# Final_5_1.net
KiCad netlist of a schematic drawn in EAGLE
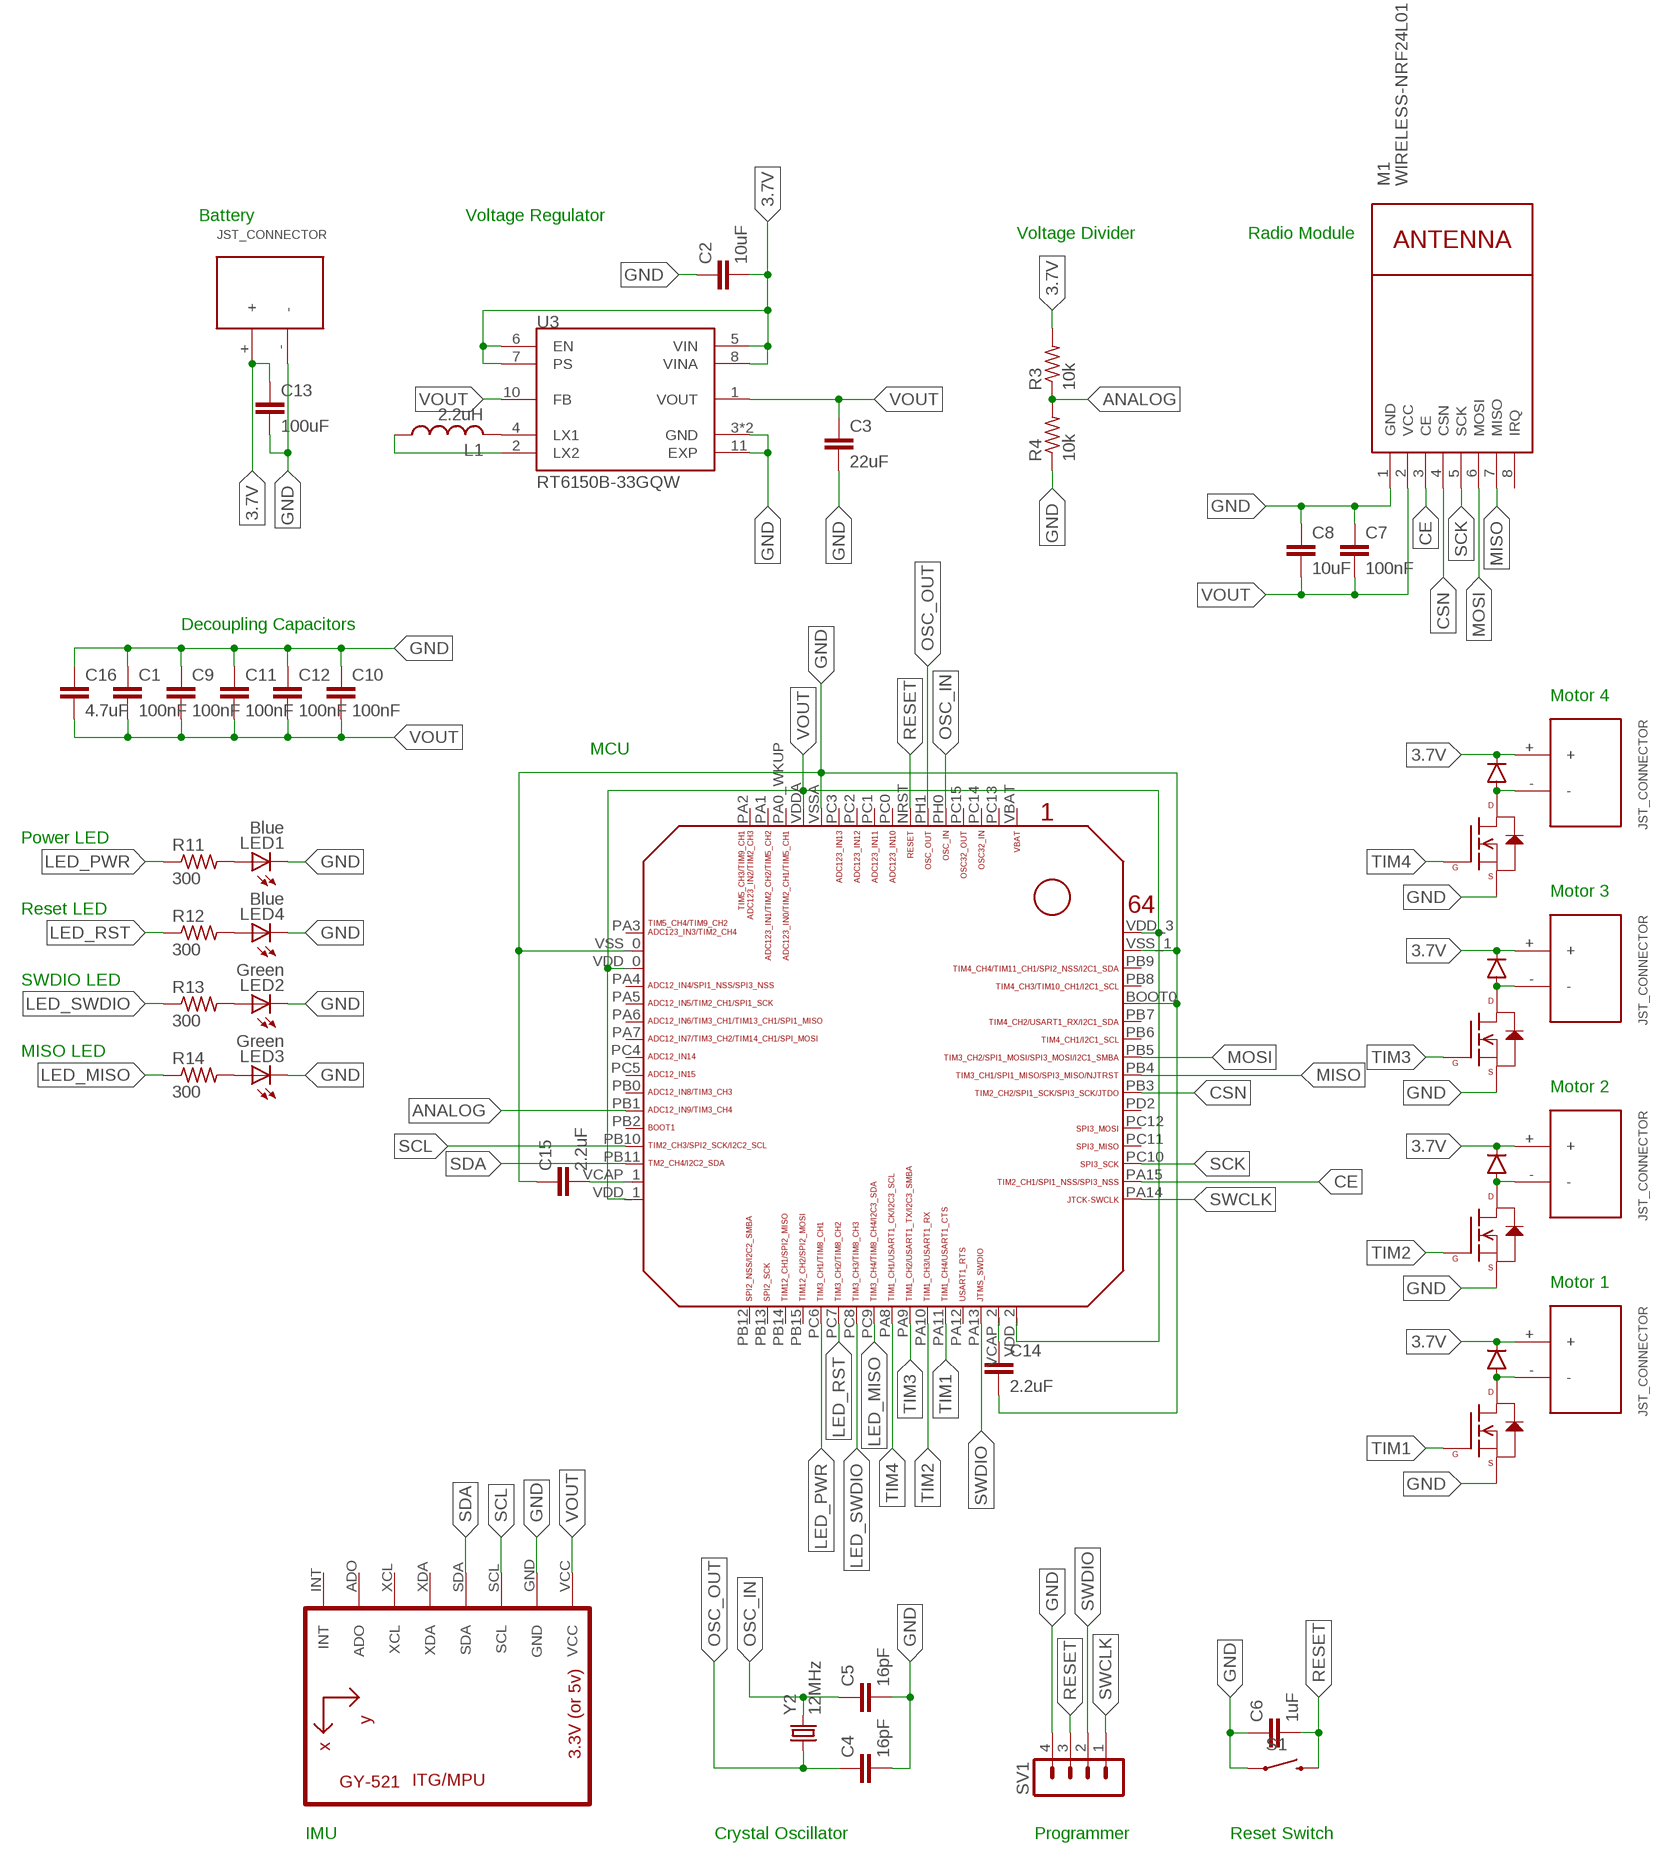
[diagram p0: schematic, sheet 1]

(export (version "E")
  (design (tool "Eeschema 10.0.6"))
  (components
    (comp (ref "C1")
      (value "100nF")
      (footprint "eagle-import:C0603")
      (libsource (lib "eagle-import") (part "rcl_334_C-EUC0603"))
    )
    (comp (ref "C2")
      (value "10uF")
      (footprint "eagle-import:C0603")
      (libsource (lib "eagle-import") (part "rcl_334_C-EUC0603"))
    )
    (comp (ref "C3")
      (value "22uF")
      (footprint "eagle-import:C0603")
      (libsource (lib "eagle-import") (part "rcl_334_C-EUC0603"))
    )
    (comp (ref "C4")
      (value "16pF")
      (footprint "eagle-import:C0603")
      (libsource (lib "eagle-import") (part "rcl_334_C-EUC0603"))
    )
    (comp (ref "C5")
      (value "16pF")
      (footprint "eagle-import:C0603")
      (libsource (lib "eagle-import") (part "rcl_334_C-EUC0603"))
    )
    (comp (ref "C6")
      (value "1uF")
      (footprint "eagle-import:C0603")
      (libsource (lib "eagle-import") (part "rcl_334_C-EUC0603"))
    )
    (comp (ref "C7")
      (value "100nF")
      (footprint "eagle-import:C0603")
      (libsource (lib "eagle-import") (part "rcl_334_C-EUC0603"))
    )
    (comp (ref "C8")
      (value "10uF")
      (footprint "eagle-import:C0603")
      (libsource (lib "eagle-import") (part "rcl_334_C-EUC0603"))
    )
    (comp (ref "C9")
      (value "100nF")
      (footprint "eagle-import:C0603")
      (libsource (lib "eagle-import") (part "rcl_334_C-EUC0603"))
    )
    (comp (ref "C10")
      (value "100nF")
      (footprint "eagle-import:C0603")
      (libsource (lib "eagle-import") (part "rcl_334_C-EUC0603"))
    )
    (comp (ref "C11")
      (value "100nF")
      (footprint "eagle-import:C0603")
      (libsource (lib "eagle-import") (part "rcl_334_C-EUC0603"))
    )
    (comp (ref "C12")
      (value "100nF")
      (footprint "eagle-import:C0603")
      (libsource (lib "eagle-import") (part "rcl_334_C-EUC0603"))
    )
    (comp (ref "C13")
      (value "100uF")
      (footprint "eagle-import:C1206")
      (libsource (lib "eagle-import") (part "rcl_334_C-EUC1206"))
    )
    (comp (ref "C14")
      (value "2.2uF")
      (footprint "eagle-import:C0603")
      (libsource (lib "eagle-import") (part "C-EUC0603"))
    )
    (comp (ref "C15")
      (value "2.2uF")
      (footprint "eagle-import:C0603")
      (libsource (lib "eagle-import") (part "C-EUC0603"))
    )
    (comp (ref "C16")
      (value "4.7uF")
      (footprint "eagle-import:C0603")
      (libsource (lib "eagle-import") (part "rcl_334_C-EUC0603"))
    )
    (comp (ref "L1")
      (value "2.2uH")
      (footprint "eagle-import:L0603")
      (libsource (lib "eagle-import") (part "L-USL0603"))
    )
    (comp (ref "LED1")
      (value "Blue")
      (footprint "eagle-import:CHIP-LED0603")
      (libsource (lib "eagle-import") (part "LEDCHIP-LED0603"))
    )
    (comp (ref "LED2")
      (value "Green")
      (footprint "eagle-import:CHIP-LED0603")
      (libsource (lib "eagle-import") (part "LEDCHIP-LED0603"))
    )
    (comp (ref "LED3")
      (value "Green")
      (footprint "eagle-import:CHIP-LED0603")
      (libsource (lib "eagle-import") (part "LEDCHIP-LED0603"))
    )
    (comp (ref "LED4")
      (value "Blue")
      (footprint "eagle-import:CHIP-LED0603")
      (libsource (lib "eagle-import") (part "LEDCHIP-LED0603"))
    )
    (comp (ref "M1")
      (value "WIRELESS-NRF24L01")
      (footprint "eagle-import:WIRELESS-NRF24L01")
      (libsource (lib "eagle-import") (part "WIRELESS-NRF24L01"))
    )
    (comp (ref "R3")
      (value "10k")
      (footprint "eagle-import:R0603")
      (libsource (lib "eagle-import") (part "R-US_R0603"))
    )
    (comp (ref "R4")
      (value "10k")
      (footprint "eagle-import:R0603")
      (libsource (lib "eagle-import") (part "R-US_R0603"))
    )
    (comp (ref "R11")
      (value "300")
      (footprint "eagle-import:R0603")
      (libsource (lib "eagle-import") (part "R-US_R0603"))
    )
    (comp (ref "R12")
      (value "300")
      (footprint "eagle-import:R0603")
      (libsource (lib "eagle-import") (part "R-US_R0603"))
    )
    (comp (ref "R13")
      (value "300")
      (footprint "eagle-import:R0603")
      (libsource (lib "eagle-import") (part "R-US_R0603"))
    )
    (comp (ref "R14")
      (value "300")
      (footprint "eagle-import:R0603")
      (libsource (lib "eagle-import") (part "R-US_R0603"))
    )
    (comp (ref "S1")
      (value "SWITCH-MOMENTARY-2SMD")
      (footprint "eagle-import:TACTILE-SWITCH-SMD")
      (libsource (lib "eagle-import") (part "SWITCH-MOMENTARY-2SMD"))
    )
    (comp (ref "SV1")
      (value "MA04-1")
      (footprint "eagle-import:MA04-1")
      (libsource (lib "eagle-import") (part "MA04-1"))
    )
    (comp (ref "U$1")
      (value "STM32F405/415_LQFP64")
      (footprint "eagle-import:STM32F405_415_LQFP64")
      (libsource (lib "eagle-import") (part "STM32F405/415_LQFP64"))
    )
    (comp (ref "U$2")
      (value "JST_CONNECTOR_FEMALE")
      (footprint "eagle-import:JST_CONNECTOR_FEMALE")
      (libsource (lib "eagle-import") (part "JST_CONNECTOR_FEMALE"))
    )
    (comp (ref "U$3")
      (value "JST_CONNECTOR_FEMALE")
      (footprint "eagle-import:JST_CONNECTOR_FEMALE")
      (libsource (lib "eagle-import") (part "JST_CONNECTOR_FEMALE"))
    )
    (comp (ref "U$4")
      (value "JST_CONNECTOR_FEMALE")
      (footprint "eagle-import:JST_CONNECTOR_FEMALE")
      (libsource (lib "eagle-import") (part "JST_CONNECTOR_FEMALE"))
    )
    (comp (ref "U$5")
      (value "JST_CONNECTOR_FEMALE")
      (footprint "eagle-import:JST_CONNECTOR_FEMALE")
      (libsource (lib "eagle-import") (part "JST_CONNECTOR_FEMALE"))
    )
    (comp (ref "U$6")
      (value "JST_CONNECTOR_FEMALE")
      (footprint "eagle-import:JST_CONNECTOR_FEMALE")
      (libsource (lib "eagle-import") (part "JST_CONNECTOR_FEMALE"))
    )
    (comp (ref "U$7")
      (value "N-CHANNEL-MOSFET-IRLML6244TRPBF")
      (footprint "eagle-import:SOT23-3")
      (libsource (lib "eagle-import") (part "N-CHANNEL-MOSFET-IRLML6244TRPBF"))
    )
    (comp (ref "U$8")
      (value "N-CHANNEL-MOSFET-IRLML6244TRPBF")
      (footprint "eagle-import:SOT23-3")
      (libsource (lib "eagle-import") (part "N-CHANNEL-MOSFET-IRLML6244TRPBF"))
    )
    (comp (ref "U$9")
      (value "N-CHANNEL-MOSFET-IRLML6244TRPBF")
      (footprint "eagle-import:SOT23-3")
      (libsource (lib "eagle-import") (part "N-CHANNEL-MOSFET-IRLML6244TRPBF"))
    )
    (comp (ref "U$10")
      (value "N-CHANNEL-MOSFET-IRLML6244TRPBF")
      (footprint "eagle-import:SOT23-3")
      (libsource (lib "eagle-import") (part "N-CHANNEL-MOSFET-IRLML6244TRPBF"))
    )
    (comp (ref "U$11")
      (value "DB2W40300L")
      (footprint "eagle-import:MINI2-F3-B")
      (libsource (lib "eagle-import") (part "DB2W40300L"))
    )
    (comp (ref "U$12")
      (value "DB2W40300L")
      (footprint "eagle-import:MINI2-F3-B")
      (libsource (lib "eagle-import") (part "DB2W40300L"))
    )
    (comp (ref "U$13")
      (value "DB2W40300L")
      (footprint "eagle-import:MINI2-F3-B")
      (libsource (lib "eagle-import") (part "DB2W40300L"))
    )
    (comp (ref "U$14")
      (value "DB2W40300L")
      (footprint "eagle-import:MINI2-F3-B")
      (libsource (lib "eagle-import") (part "DB2W40300L"))
    )
    (comp (ref "U2")
      (value "GY-521MPU6050")
      (footprint "eagle-import:GY-521")
      (libsource (lib "eagle-import") (part "GY-521MPU6050"))
    )
    (comp (ref "U3")
      (value "RT6150B-33GQW")
      (footprint "eagle-import:SON50P250X250X80-11N")
      (fields (field (name "DIGI-KEY_PART_NUMBER") "RT6150B-33GQWCT-ND") (field (name "MF") "Richtek USA"))
      (libsource (lib "eagle-import") (part "RT6150B-33GQW"))
    )
    (comp (ref "Y2")
      (value "12MHz")
      (footprint "eagle-import:HC49UP")
      (libsource (lib "eagle-import") (part "CRYSTALSMD"))
    )
  )
  (nets
    (net (code "1") (name "3.7V") (class "Default")
      (node (ref "C13") (pin "1") (pinfunction "1_1") (pintype "passive"))
      (node (ref "C2") (pin "2") (pinfunction "2_2") (pintype "passive"))
      (node (ref "R3") (pin "2") (pinfunction "2_2") (pintype "passive"))
      (node (ref "U$11") (pin "NEG") (pinfunction "GPIN_NEG") (pintype "passive"))
      (node (ref "U$12") (pin "NEG") (pinfunction "GPIN_NEG") (pintype "passive"))
      (node (ref "U$13") (pin "NEG") (pinfunction "GPIN_NEG") (pintype "passive"))
      (node (ref "U$14") (pin "NEG") (pinfunction "GPIN_NEG") (pintype "passive"))
      (node (ref "U$2") (pin "+") (pinfunction "+_+") (pintype "bidirectional"))
      (node (ref "U$3") (pin "+") (pinfunction "+_+") (pintype "bidirectional"))
      (node (ref "U$4") (pin "+") (pinfunction "+_+") (pintype "bidirectional"))
      (node (ref "U$5") (pin "+") (pinfunction "+_+") (pintype "bidirectional"))
      (node (ref "U$6") (pin "+") (pinfunction "+_+") (pintype "bidirectional"))
      (node (ref "U3") (pin "5") (pinfunction "VIN_5") (pintype "power_in"))
      (node (ref "U3") (pin "6") (pinfunction "EN_6") (pintype "input"))
      (node (ref "U3") (pin "7") (pinfunction "PS_7") (pintype "input"))
      (node (ref "U3") (pin "8") (pinfunction "VINA_8") (pintype "power_in"))
    )
    (net (code "2") (name "ANALOG") (class "Default")
      (node (ref "R3") (pin "1") (pinfunction "1_1") (pintype "passive"))
      (node (ref "R4") (pin "2") (pinfunction "2_2") (pintype "passive"))
      (node (ref "U$1") (pin "PB1") (pinfunction "PB1_PB1") (pintype "bidirectional"))
    )
    (net (code "3") (name "CE") (class "Default")
      (node (ref "M1") (pin "3") (pinfunction "CE_3") (pintype "bidirectional"))
      (node (ref "U$1") (pin "PA15") (pinfunction "PA15_PA15") (pintype "bidirectional"))
    )
    (net (code "4") (name "CSN") (class "Default")
      (node (ref "M1") (pin "4") (pinfunction "CSN_4") (pintype "bidirectional"))
      (node (ref "U$1") (pin "PB3") (pinfunction "PB3_PB3") (pintype "bidirectional"))
    )
    (net (code "5") (name "GND") (class "Default")
      (node (ref "C1") (pin "1") (pinfunction "1_1") (pintype "passive"))
      (node (ref "C10") (pin "1") (pinfunction "1_1") (pintype "passive"))
      (node (ref "C11") (pin "1") (pinfunction "1_1") (pintype "passive"))
      (node (ref "C12") (pin "1") (pinfunction "1_1") (pintype "passive"))
      (node (ref "C13") (pin "2") (pinfunction "2_2") (pintype "passive"))
      (node (ref "C14") (pin "2") (pinfunction "2_2") (pintype "passive"))
      (node (ref "C15") (pin "1") (pinfunction "1_1") (pintype "passive"))
      (node (ref "C16") (pin "1") (pinfunction "1_1") (pintype "passive"))
      (node (ref "C2") (pin "1") (pinfunction "1_1") (pintype "passive"))
      (node (ref "C3") (pin "2") (pinfunction "2_2") (pintype "passive"))
      (node (ref "C4") (pin "2") (pinfunction "2_2") (pintype "passive"))
      (node (ref "C5") (pin "2") (pinfunction "2_2") (pintype "passive"))
      (node (ref "C6") (pin "1") (pinfunction "1_1") (pintype "passive"))
      (node (ref "C7") (pin "1") (pinfunction "1_1") (pintype "passive"))
      (node (ref "C8") (pin "1") (pinfunction "1_1") (pintype "passive"))
      (node (ref "C9") (pin "1") (pinfunction "1_1") (pintype "passive"))
      (node (ref "LED1") (pin "C") (pinfunction "C_C") (pintype "passive"))
      (node (ref "LED2") (pin "C") (pinfunction "C_C") (pintype "passive"))
      (node (ref "LED3") (pin "C") (pinfunction "C_C") (pintype "passive"))
      (node (ref "LED4") (pin "C") (pinfunction "C_C") (pintype "passive"))
      (node (ref "M1") (pin "1") (pinfunction "GND_1") (pintype "power_in"))
      (node (ref "R4") (pin "1") (pinfunction "1_1") (pintype "passive"))
      (node (ref "S1") (pin "1") (pinfunction "1_1") (pintype "passive"))
      (node (ref "SV1") (pin "4") (pinfunction "4_4") (pintype "passive"))
      (node (ref "U$1") (pin "BOOT0") (pinfunction "BOOT0_BOOT0") (pintype "bidirectional"))
      (node (ref "U$1") (pin "VSSA") (pinfunction "VSSA_VSSA") (pintype "bidirectional"))
      (node (ref "U$1") (pin "VSS_0") (pinfunction "VSS_0_VSS_0") (pintype "bidirectional"))
      (node (ref "U$1") (pin "VSS_1") (pinfunction "VSS_1_VSS_1") (pintype "bidirectional"))
      (node (ref "U$10") (pin "2") (pinfunction "S_2") (pintype "passive"))
      (node (ref "U$2") (pin "-") (pinfunction "-_-") (pintype "bidirectional"))
      (node (ref "U$7") (pin "2") (pinfunction "S_2") (pintype "passive"))
      (node (ref "U$8") (pin "2") (pinfunction "S_2") (pintype "passive"))
      (node (ref "U$9") (pin "2") (pinfunction "S_2") (pintype "passive"))
      (node (ref "U2") (pin "GND") (pinfunction "GND_GND") (pintype "bidirectional"))
      (node (ref "U3") (pin "11") (pinfunction "EXP_11") (pintype "passive"))
      (node (ref "U3") (pin "3") (pinfunction "GND_3") (pintype "power_in"))
      (node (ref "U3") (pin "9") (pinfunction "GND_9") (pintype "power_in"))
    )
    (net (code "6") (name "LED_MISO") (class "Default")
      (node (ref "R14") (pin "1") (pinfunction "1_1") (pintype "passive"))
      (node (ref "U$1") (pin "PC9") (pinfunction "PC9_PC9") (pintype "bidirectional"))
    )
    (net (code "7") (name "LED_PWR") (class "Default")
      (node (ref "R11") (pin "1") (pinfunction "1_1") (pintype "passive"))
      (node (ref "U$1") (pin "PC6") (pinfunction "PC6_PC6") (pintype "bidirectional"))
    )
    (net (code "8") (name "LED_RST") (class "Default")
      (node (ref "R12") (pin "1") (pinfunction "1_1") (pintype "passive"))
      (node (ref "U$1") (pin "PC7") (pinfunction "PC7_PC7") (pintype "bidirectional"))
    )
    (net (code "9") (name "LED_SWDIO") (class "Default")
      (node (ref "R13") (pin "1") (pinfunction "1_1") (pintype "passive"))
      (node (ref "U$1") (pin "PC8") (pinfunction "PC8_PC8") (pintype "bidirectional"))
    )
    (net (code "10") (name "MISO") (class "Default")
      (node (ref "M1") (pin "7") (pinfunction "MISO_7") (pintype "bidirectional"))
      (node (ref "U$1") (pin "PB4") (pinfunction "PB4_PB4") (pintype "bidirectional"))
    )
    (net (code "11") (name "MOSI") (class "Default")
      (node (ref "M1") (pin "6") (pinfunction "MOSI_6") (pintype "bidirectional"))
      (node (ref "U$1") (pin "PB5") (pinfunction "PB5_PB5") (pintype "bidirectional"))
    )
    (net (code "12") (name "Net-(C14-Pad1)") (class "Default")
      (node (ref "C14") (pin "1") (pinfunction "1_1") (pintype "passive"))
      (node (ref "U$1") (pin "VCAP_2") (pinfunction "VCAP_2_VCAP_2") (pintype "bidirectional"))
    )
    (net (code "13") (name "Net-(C15-Pad2)") (class "Default")
      (node (ref "C15") (pin "2") (pinfunction "2_2") (pintype "passive"))
      (node (ref "U$1") (pin "VCAP_1") (pinfunction "VCAP_1_VCAP_1") (pintype "bidirectional"))
    )
    (net (code "14") (name "Net-(LED1-PadA)") (class "Default")
      (node (ref "LED1") (pin "A") (pinfunction "A_A") (pintype "passive"))
      (node (ref "R11") (pin "2") (pinfunction "2_2") (pintype "passive"))
    )
    (net (code "15") (name "Net-(LED2-PadA)") (class "Default")
      (node (ref "LED2") (pin "A") (pinfunction "A_A") (pintype "passive"))
      (node (ref "R13") (pin "2") (pinfunction "2_2") (pintype "passive"))
    )
    (net (code "16") (name "Net-(LED3-PadA)") (class "Default")
      (node (ref "LED3") (pin "A") (pinfunction "A_A") (pintype "passive"))
      (node (ref "R14") (pin "2") (pinfunction "2_2") (pintype "passive"))
    )
    (net (code "17") (name "Net-(LED4-PadA)") (class "Default")
      (node (ref "LED4") (pin "A") (pinfunction "A_A") (pintype "passive"))
      (node (ref "R12") (pin "2") (pinfunction "2_2") (pintype "passive"))
    )
    (net (code "18") (name "Net-(U$10-D)") (class "Default")
      (node (ref "U$10") (pin "3") (pinfunction "D_3") (pintype "passive"))
      (node (ref "U$14") (pin "POS") (pinfunction "PPIN_POS") (pintype "passive"))
      (node (ref "U$6") (pin "-") (pinfunction "-_-") (pintype "bidirectional"))
    )
    (net (code "19") (name "Net-(U$11-PPIN)") (class "Default")
      (node (ref "U$11") (pin "POS") (pinfunction "PPIN_POS") (pintype "passive"))
      (node (ref "U$3") (pin "-") (pinfunction "-_-") (pintype "bidirectional"))
      (node (ref "U$9") (pin "3") (pinfunction "D_3") (pintype "passive"))
    )
    (net (code "20") (name "Net-(U$12-PPIN)") (class "Default")
      (node (ref "U$12") (pin "POS") (pinfunction "PPIN_POS") (pintype "passive"))
      (node (ref "U$5") (pin "-") (pinfunction "-_-") (pintype "bidirectional"))
      (node (ref "U$8") (pin "3") (pinfunction "D_3") (pintype "passive"))
    )
    (net (code "21") (name "Net-(U$13-PPIN)") (class "Default")
      (node (ref "U$13") (pin "POS") (pinfunction "PPIN_POS") (pintype "passive"))
      (node (ref "U$4") (pin "-") (pinfunction "-_-") (pintype "bidirectional"))
      (node (ref "U$7") (pin "3") (pinfunction "D_3") (pintype "passive"))
    )
    (net (code "22") (name "Net-(U3-LX1)") (class "Default")
      (node (ref "L1") (pin "2") (pinfunction "2_2") (pintype "passive"))
      (node (ref "U3") (pin "4") (pinfunction "LX1_4") (pintype "passive"))
    )
    (net (code "23") (name "Net-(U3-LX2)") (class "Default")
      (node (ref "L1") (pin "1") (pinfunction "1_1") (pintype "passive"))
      (node (ref "U3") (pin "2") (pinfunction "LX2_2") (pintype "passive"))
    )
    (net (code "24") (name "OSC_IN") (class "Default")
      (node (ref "C5") (pin "1") (pinfunction "1_1") (pintype "passive"))
      (node (ref "U$1") (pin "PH0") (pinfunction "PH0_PH0") (pintype "bidirectional"))
      (node (ref "Y2") (pin "2") (pinfunction "2_2") (pintype "passive"))
    )
    (net (code "25") (name "OSC_OUT") (class "Default")
      (node (ref "C4") (pin "1") (pinfunction "1_1") (pintype "passive"))
      (node (ref "U$1") (pin "PH1") (pinfunction "PH1_PH1") (pintype "bidirectional"))
      (node (ref "Y2") (pin "1") (pinfunction "1_1") (pintype "passive"))
    )
    (net (code "26") (name "RESET") (class "Default")
      (node (ref "C6") (pin "2") (pinfunction "2_2") (pintype "passive"))
      (node (ref "S1") (pin "3") (pinfunction "2_3") (pintype "passive"))
      (node (ref "SV1") (pin "3") (pinfunction "3_3") (pintype "passive"))
      (node (ref "U$1") (pin "NRST") (pinfunction "NRST_NRST") (pintype "bidirectional"))
    )
    (net (code "27") (name "SCK") (class "Default")
      (node (ref "M1") (pin "5") (pinfunction "SCK_5") (pintype "bidirectional"))
      (node (ref "U$1") (pin "PC10") (pinfunction "PC10_PC10") (pintype "bidirectional"))
    )
    (net (code "28") (name "SCL") (class "Default")
      (node (ref "U$1") (pin "PB10") (pinfunction "PB10_PB10") (pintype "bidirectional"))
      (node (ref "U2") (pin "SCL") (pinfunction "SCL_SCL") (pintype "bidirectional"))
    )
    (net (code "29") (name "SDA") (class "Default")
      (node (ref "U$1") (pin "PB11") (pinfunction "PB11_PB11") (pintype "bidirectional"))
      (node (ref "U2") (pin "SDA") (pinfunction "SDA_SDA") (pintype "bidirectional"))
    )
    (net (code "30") (name "SWCLK") (class "Default")
      (node (ref "SV1") (pin "1") (pinfunction "1_1") (pintype "passive"))
      (node (ref "U$1") (pin "PA14") (pinfunction "PA14_PA14") (pintype "bidirectional"))
    )
    (net (code "31") (name "SWDIO") (class "Default")
      (node (ref "SV1") (pin "2") (pinfunction "2_2") (pintype "passive"))
      (node (ref "U$1") (pin "PA13") (pinfunction "PA13_PA13") (pintype "bidirectional"))
    )
    (net (code "32") (name "TIM1") (class "Default")
      (node (ref "U$1") (pin "PA11") (pinfunction "PA11_PA11") (pintype "bidirectional"))
      (node (ref "U$10") (pin "1") (pinfunction "G_1") (pintype "passive"))
    )
    (net (code "33") (name "TIM2") (class "Default")
      (node (ref "U$1") (pin "PA10") (pinfunction "PA10_PA10") (pintype "bidirectional"))
      (node (ref "U$8") (pin "1") (pinfunction "G_1") (pintype "passive"))
    )
    (net (code "34") (name "TIM3") (class "Default")
      (node (ref "U$1") (pin "PA9") (pinfunction "PA9_PA9") (pintype "bidirectional"))
      (node (ref "U$7") (pin "1") (pinfunction "G_1") (pintype "passive"))
    )
    (net (code "35") (name "TIM4") (class "Default")
      (node (ref "U$1") (pin "PA8") (pinfunction "PA8_PA8") (pintype "bidirectional"))
      (node (ref "U$9") (pin "1") (pinfunction "G_1") (pintype "passive"))
    )
    (net (code "36") (name "VOUT") (class "Default")
      (node (ref "C1") (pin "2") (pinfunction "2_2") (pintype "passive"))
      (node (ref "C10") (pin "2") (pinfunction "2_2") (pintype "passive"))
      (node (ref "C11") (pin "2") (pinfunction "2_2") (pintype "passive"))
      (node (ref "C12") (pin "2") (pinfunction "2_2") (pintype "passive"))
      (node (ref "C16") (pin "2") (pinfunction "2_2") (pintype "passive"))
      (node (ref "C3") (pin "1") (pinfunction "1_1") (pintype "passive"))
      (node (ref "C7") (pin "2") (pinfunction "2_2") (pintype "passive"))
      (node (ref "C8") (pin "2") (pinfunction "2_2") (pintype "passive"))
      (node (ref "C9") (pin "2") (pinfunction "2_2") (pintype "passive"))
      (node (ref "M1") (pin "2") (pinfunction "VCC_2") (pintype "power_in"))
      (node (ref "U$1") (pin "VDDA") (pinfunction "VDDA_VDDA") (pintype "bidirectional"))
      (node (ref "U$1") (pin "VDD_0") (pinfunction "VDD_0_VDD_0") (pintype "bidirectional"))
      (node (ref "U$1") (pin "VDD_1") (pinfunction "VDD_1_VDD_1") (pintype "bidirectional"))
      (node (ref "U$1") (pin "VDD_2") (pinfunction "VDD_2_VDD_2") (pintype "bidirectional"))
      (node (ref "U$1") (pin "VDD_3") (pinfunction "VDD_3_VDD_3") (pintype "bidirectional"))
      (node (ref "U2") (pin "VCC") (pinfunction "VCC_VCC") (pintype "bidirectional"))
      (node (ref "U3") (pin "1") (pinfunction "VOUT_1") (pintype "output"))
      (node (ref "U3") (pin "10") (pinfunction "FB_10") (pintype "input"))
    )
    (net (code "37") (name "unconnected-(M1-IRQ-Pad8)") (class "Default")
      (node (ref "M1") (pin "8") (pinfunction "IRQ_8") (pintype "bidirectional"))
    )
    (net (code "38") (name "unconnected-(U$1-PA0_AKUP-PadPA0_WKUP)") (class "Default")
      (node (ref "U$1") (pin "PA0_WKUP") (pinfunction "PA0_AKUP_PA0_WKUP") (pintype "bidirectional"))
    )
    (net (code "39") (name "unconnected-(U$1-PadPA1)") (class "Default")
      (node (ref "U$1") (pin "PA1") (pinfunction "PA1_PA1") (pintype "bidirectional"))
    )
    (net (code "40") (name "unconnected-(U$1-PadPA2)") (class "Default")
      (node (ref "U$1") (pin "PA2") (pinfunction "PA2_PA2") (pintype "bidirectional"))
    )
    (net (code "41") (name "unconnected-(U$1-PadPA3)") (class "Default")
      (node (ref "U$1") (pin "PA3") (pinfunction "PA3_PA3") (pintype "bidirectional"))
    )
    (net (code "42") (name "unconnected-(U$1-PadPA4)") (class "Default")
      (node (ref "U$1") (pin "PA4") (pinfunction "PA4_PA4") (pintype "bidirectional"))
    )
    (net (code "43") (name "unconnected-(U$1-PadPA5)") (class "Default")
      (node (ref "U$1") (pin "PA5") (pinfunction "PA5_PA5") (pintype "bidirectional"))
    )
    (net (code "44") (name "unconnected-(U$1-PadPA6)") (class "Default")
      (node (ref "U$1") (pin "PA6") (pinfunction "PA6_PA6") (pintype "bidirectional"))
    )
    (net (code "45") (name "unconnected-(U$1-PadPA7)") (class "Default")
      (node (ref "U$1") (pin "PA7") (pinfunction "PA7_PA7") (pintype "bidirectional"))
    )
    (net (code "46") (name "unconnected-(U$1-PadPA12)") (class "Default")
      (node (ref "U$1") (pin "PA12") (pinfunction "PA12_PA12") (pintype "bidirectional"))
    )
    (net (code "47") (name "unconnected-(U$1-PadPB0)") (class "Default")
      (node (ref "U$1") (pin "PB0") (pinfunction "PB0_PB0") (pintype "bidirectional"))
    )
    (net (code "48") (name "unconnected-(U$1-PadPB2)") (class "Default")
      (node (ref "U$1") (pin "PB2") (pinfunction "PB2_PB2") (pintype "bidirectional"))
    )
    (net (code "49") (name "unconnected-(U$1-PadPB6)") (class "Default")
      (node (ref "U$1") (pin "PB6") (pinfunction "PB6_PB6") (pintype "bidirectional"))
    )
    (net (code "50") (name "unconnected-(U$1-PadPB7)") (class "Default")
      (node (ref "U$1") (pin "PB7") (pinfunction "PB7_PB7") (pintype "bidirectional"))
    )
    (net (code "51") (name "unconnected-(U$1-PadPB8)") (class "Default")
      (node (ref "U$1") (pin "PB8") (pinfunction "PB8_PB8") (pintype "bidirectional"))
    )
    (net (code "52") (name "unconnected-(U$1-PadPB9)") (class "Default")
      (node (ref "U$1") (pin "PB9") (pinfunction "PB9_PB9") (pintype "bidirectional"))
    )
    (net (code "53") (name "unconnected-(U$1-PadPB12)") (class "Default")
      (node (ref "U$1") (pin "PB12") (pinfunction "PB12_PB12") (pintype "bidirectional"))
    )
    (net (code "54") (name "unconnected-(U$1-PadPB13)") (class "Default")
      (node (ref "U$1") (pin "PB13") (pinfunction "PB13_PB13") (pintype "bidirectional"))
    )
    (net (code "55") (name "unconnected-(U$1-PadPB14)") (class "Default")
      (node (ref "U$1") (pin "PB14") (pinfunction "PB14_PB14") (pintype "bidirectional"))
    )
    (net (code "56") (name "unconnected-(U$1-PadPB15)") (class "Default")
      (node (ref "U$1") (pin "PB15") (pinfunction "PB15_PB15") (pintype "bidirectional"))
    )
    (net (code "57") (name "unconnected-(U$1-PadPC0)") (class "Default")
      (node (ref "U$1") (pin "PC0") (pinfunction "PC0_PC0") (pintype "bidirectional"))
    )
    (net (code "58") (name "unconnected-(U$1-PadPC1)") (class "Default")
      (node (ref "U$1") (pin "PC1") (pinfunction "PC1_PC1") (pintype "bidirectional"))
    )
    (net (code "59") (name "unconnected-(U$1-PadPC2)") (class "Default")
      (node (ref "U$1") (pin "PC2") (pinfunction "PC2_PC2") (pintype "bidirectional"))
    )
    (net (code "60") (name "unconnected-(U$1-PadPC3)") (class "Default")
      (node (ref "U$1") (pin "PC3") (pinfunction "PC3_PC3") (pintype "bidirectional"))
    )
    (net (code "61") (name "unconnected-(U$1-PadPC4)") (class "Default")
      (node (ref "U$1") (pin "PC4") (pinfunction "PC4_PC4") (pintype "bidirectional"))
    )
    (net (code "62") (name "unconnected-(U$1-PadPC5)") (class "Default")
      (node (ref "U$1") (pin "PC5") (pinfunction "PC5_PC5") (pintype "bidirectional"))
    )
    (net (code "63") (name "unconnected-(U$1-PadPC11)") (class "Default")
      (node (ref "U$1") (pin "PC11") (pinfunction "PC11_PC11") (pintype "bidirectional"))
    )
    (net (code "64") (name "unconnected-(U$1-PadPC12)") (class "Default")
      (node (ref "U$1") (pin "PC12") (pinfunction "PC12_PC12") (pintype "bidirectional"))
    )
    (net (code "65") (name "unconnected-(U$1-PadPC13)") (class "Default")
      (node (ref "U$1") (pin "PC13") (pinfunction "PC13_PC13") (pintype "bidirectional"))
    )
    (net (code "66") (name "unconnected-(U$1-PadPC14)") (class "Default")
      (node (ref "U$1") (pin "PC14") (pinfunction "PC14_PC14") (pintype "bidirectional"))
    )
    (net (code "67") (name "unconnected-(U$1-PadPC15)") (class "Default")
      (node (ref "U$1") (pin "PC15") (pinfunction "PC15_PC15") (pintype "bidirectional"))
    )
    (net (code "68") (name "unconnected-(U$1-PadPD2)") (class "Default")
      (node (ref "U$1") (pin "PD2") (pinfunction "PD2_PD2") (pintype "bidirectional"))
    )
    (net (code "69") (name "unconnected-(U$1-PadVBAT)") (class "Default")
      (node (ref "U$1") (pin "VBAT") (pinfunction "VBAT_VBAT") (pintype "bidirectional"))
    )
    (net (code "70") (name "unconnected-(U2-PadADO)") (class "Default")
      (node (ref "U2") (pin "ADO") (pinfunction "ADO_ADO") (pintype "bidirectional"))
    )
    (net (code "71") (name "unconnected-(U2-PadINT)") (class "Default")
      (node (ref "U2") (pin "INT") (pinfunction "INT_INT") (pintype "bidirectional"))
    )
    (net (code "72") (name "unconnected-(U2-PadXCL)") (class "Default")
      (node (ref "U2") (pin "XCL") (pinfunction "XCL_XCL") (pintype "bidirectional"))
    )
    (net (code "73") (name "unconnected-(U2-PadXDA)") (class "Default")
      (node (ref "U2") (pin "XDA") (pinfunction "XDA_XDA") (pintype "bidirectional"))
    )
  )
)
